# 1-Schematic_Indoor_meteo_sensor.net
KiCad netlist of a schematic drawn in EasyEDA
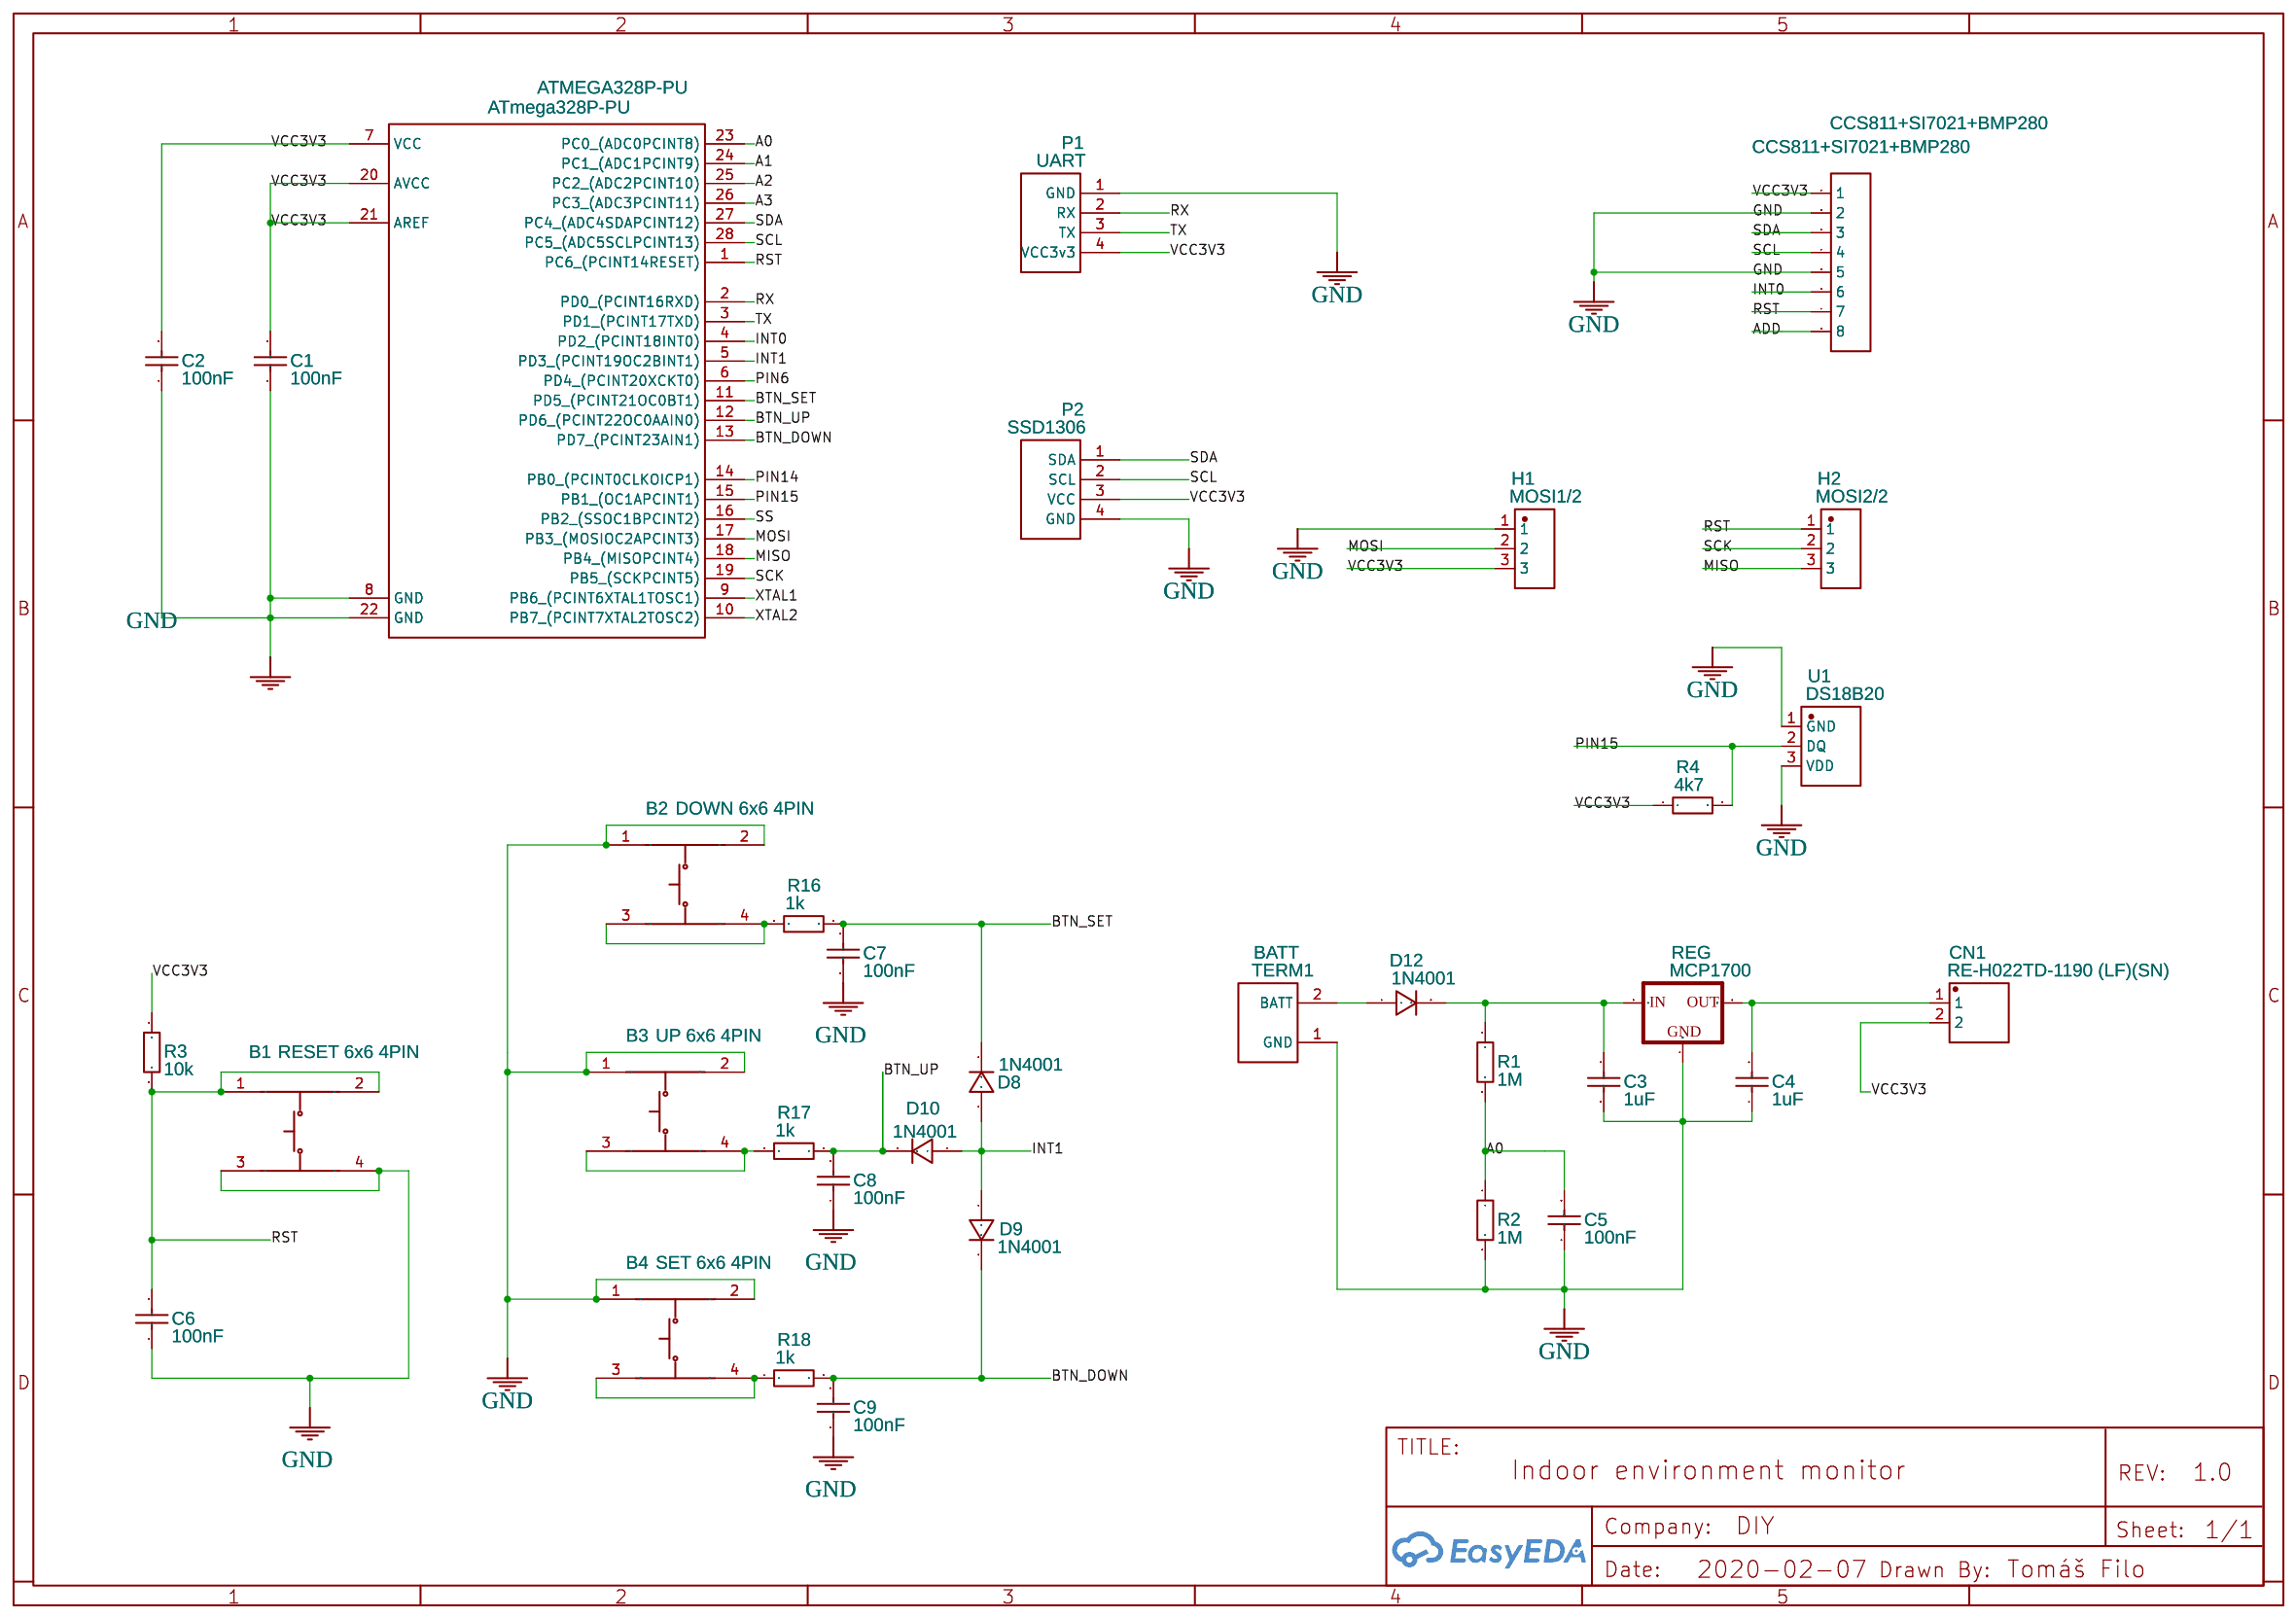
[diagram p0: schematic sheet]

(export (version "E")
  (design (tool "Eeschema 10.0.6"))
  (components
    (comp (ref "ATMEGA328P-PU") (value "ATmega328P-PU") (libsource (lib "") (part "ATmega328P-PU")))
    (comp (ref "B1")
      (value "RESET 6x6 4PIN")
      (fields
        (field (name "BOM_Manufacturer Part") "TC-1102-C-E-B")
        (field (name "BOM_Supplier Part") "C381011")
      )
      (libsource (lib "") (part "Unknown_145_-240"))
    )
    (comp (ref "B2")
      (value "DOWN 6x6 4PIN")
      (fields
        (field (name "BOM_Manufacturer Part") "TC-1102-C-E-B")
        (field (name "BOM_Supplier Part") "C381011")
      )
      (libsource (lib "") (part "Unknown_340_-365"))
    )
    (comp (ref "B3")
      (value "UP 6x6 4PIN")
      (fields
        (field (name "BOM_Manufacturer Part") "TC-1102-C-E-B")
        (field (name "BOM_Supplier Part") "C381011")
      )
      (libsource (lib "") (part "Unknown_330_-250"))
    )
    (comp (ref "B4")
      (value "SET 6x6 4PIN")
      (fields
        (field (name "BOM_Manufacturer Part") "TC-1102-C-E-B")
        (field (name "BOM_Supplier Part") "C381011")
      )
      (libsource (lib "") (part "Unknown_335_-135"))
    )
    (comp (ref "BATT")
      (value "TERM1")
      (fields
        (field (name "BOM_Manufacturer Part") "MKDSN1.5/2-5.08")
        (field (name "BOM_Supplier Part") "C91153")
      )
      (libsource (lib "") (part "Unknown_645_-295"))
    )
    (comp (ref "C1")
      (value "100nF")
      (fields
        (field (name "BOM_Manufacturer Part") "CD1H224KC9BER1E000")
        (field (name "BOM_Supplier Part") "C263191")
      )
      (libsource (lib "") (part "CD1H224KC9BER1E000"))
    )
    (comp (ref "C2")
      (value "100nF")
      (fields
        (field (name "BOM_Manufacturer Part") "CD1H224KC9BER1E000")
        (field (name "BOM_Supplier Part") "C263191")
      )
      (libsource (lib "") (part "CD1H224KC9BER1E000"))
    )
    (comp (ref "C3")
      (value "1uF")
      (fields
        (field (name "BOM_Manufacturer Part") "CD1H224KC9BER1E000")
        (field (name "BOM_Supplier Part") "C263191")
      )
      (libsource (lib "") (part "CD1H224KC9BER1E000"))
    )
    (comp (ref "C4")
      (value "1uF")
      (fields
        (field (name "BOM_Manufacturer Part") "CD1H224KC9BER1E000")
        (field (name "BOM_Supplier Part") "C263191")
      )
      (libsource (lib "") (part "CD1H224KC9BER1E000"))
    )
    (comp (ref "C5")
      (value "100nF")
      (fields
        (field (name "BOM_Manufacturer Part") "CD1H224KC9BER1E000")
        (field (name "BOM_Supplier Part") "C263191")
      )
      (libsource (lib "") (part "CD1H224KC9BER1E000"))
    )
    (comp (ref "C6")
      (value "100nF")
      (fields
        (field (name "BOM_Manufacturer Part") "CD1H224KC9BER1E000")
        (field (name "BOM_Supplier Part") "C263191")
      )
      (libsource (lib "") (part "CD1H224KC9BER1E000"))
    )
    (comp (ref "C7")
      (value "100nF")
      (fields
        (field (name "BOM_Manufacturer Part") "CD1H224KC9BER1E000")
        (field (name "BOM_Supplier Part") "C263191")
      )
      (libsource (lib "") (part "CD1H224KC9BER1E000"))
    )
    (comp (ref "C8")
      (value "100nF")
      (fields
        (field (name "BOM_Manufacturer Part") "CD1H224KC9BER1E000")
        (field (name "BOM_Supplier Part") "C263191")
      )
      (libsource (lib "") (part "CD1H224KC9BER1E000"))
    )
    (comp (ref "C9")
      (value "100nF")
      (fields
        (field (name "BOM_Manufacturer Part") "CD1H224KC9BER1E000")
        (field (name "BOM_Supplier Part") "C263191")
      )
      (libsource (lib "") (part "CD1H224KC9BER1E000"))
    )
    (comp (ref "CCS811+SI7021+BMP280")
      (value "CCS811+SI7021+BMP280")
      (fields
        (field (name "BOM_Manufacturer Part") "Female headerHDR1X8-2.54")
        (field (name "BOM_Supplier Part") "C27438")
      )
      (libsource (lib "") (part "Unknown_925_-680"))
    )
    (comp (ref "CN1")
      (value "RE-H022TD-1190 (LF)(SN)")
      (fields (field (name "BOM_Supplier Part") "C160332"))
      (libsource (lib "") (part "RE-H022TD-1190 (LF)(SN)"))
    )
    (comp (ref "D8")
      (value "1N4001")
      (fields (field (name "BOM_Supplier Part") "C169150"))
      (libsource (lib "") (part "Unknown_490_-265"))
    )
    (comp (ref "D9")
      (value "1N4001")
      (fields (field (name "BOM_Supplier Part") "C169150"))
      (libsource (lib "") (part "Unknown_490_-190"))
    )
    (comp (ref "D10")
      (value "1N4001")
      (fields (field (name "BOM_Supplier Part") "C169150"))
      (libsource (lib "") (part "Unknown_460_-230"))
    )
    (comp (ref "D12")
      (value "1N4001")
      (fields (field (name "BOM_Supplier Part") "C169150"))
      (libsource (lib "") (part "Unknown_705_-305"))
    )
    (comp (ref "H1")
      (value "MOSI1/2")
      (fields
        (field (name "BOM_Manufacturer Part") "22025403P00CKMT")
        (field (name "BOM_Supplier Part") "C146690")
      )
      (libsource (lib "") (part "22025403P00CKMT"))
    )
    (comp (ref "H2")
      (value "MOSI2/2")
      (fields
        (field (name "BOM_Manufacturer Part") "22025403P00CKMT")
        (field (name "BOM_Supplier Part") "C146690")
      )
      (libsource (lib "") (part "22025403P00CKMT"))
    )
    (comp (ref "P1")
      (value "UART")
      (fields
        (field (name "BOM_Manufacturer Part") "220S-1*4P H=8.5MM Ytype Gold-plated")
        (field (name "BOM_Supplier Part") "C124413")
      )
      (libsource (lib "") (part "Unknown_535_-700"))
    )
    (comp (ref "P2")
      (value "SSD1306")
      (fields
        (field (name "BOM_Manufacturer Part") "220S-1*4P H=8.5MM Ytype Gold-plated")
        (field (name "BOM_Supplier Part") "C124413")
      )
      (libsource (lib "") (part "Unknown_535_-565"))
    )
    (comp (ref "R1")
      (value "1M")
      (fields (field (name "BOM_Supplier Part") "C119320"))
      (libsource (lib "") (part "MF1/4W-680Ω±1% T52"))
    )
    (comp (ref "R2")
      (value "1M")
      (fields (field (name "BOM_Supplier Part") "C119320"))
      (libsource (lib "") (part "MF1/4W-680Ω±1% T52"))
    )
    (comp (ref "R3")
      (value "10k")
      (fields (field (name "BOM_Supplier Part") "C119313"))
      (libsource (lib "") (part "MF1/4W-330Ω±1% T52_1"))
    )
    (comp (ref "R4")
      (value "4k7")
      (fields (field (name "BOM_Supplier Part") "C119313"))
      (libsource (lib "") (part "MF1/4W-330Ω±1% T52"))
    )
    (comp (ref "R16")
      (value "1k")
      (fields (field (name "BOM_Supplier Part") "C119313"))
      (libsource (lib "") (part "MF1/4W-330Ω±1% T52"))
    )
    (comp (ref "R17")
      (value "1k")
      (fields (field (name "BOM_Supplier Part") "C119313"))
      (libsource (lib "") (part "MF1/4W-330Ω±1% T52"))
    )
    (comp (ref "R18")
      (value "1k")
      (fields (field (name "BOM_Supplier Part") "C119313"))
      (libsource (lib "") (part "MF1/4W-330Ω±1% T52"))
    )
    (comp (ref "REG") (value "MCP1700") (libsource (lib "") (part "Unknown_845_-295")))
    (comp (ref "U1")
      (value "DS18B20")
      (fields (field (name "BOM_Supplier Part") "C376006"))
      (libsource (lib "") (part "DS18B20"))
    )
  )
  (nets
    (net (code "1") (name "/A0") (class "Default")
      (node (ref "ATMEGA328P-PU") (pin "23") (pinfunction "PC0_(ADC0PCINT8)_23") (pintype "bidirectional"))
      (node (ref "C5") (pin "2") (pinfunction "2_2") (pintype "input"))
      (node (ref "R1") (pin "2") (pinfunction "2_2") (pintype "unspecified"))
      (node (ref "R2") (pin "1") (pinfunction "1_1") (pintype "unspecified"))
    )
    (net (code "2") (name "/A1") (class "Default")
      (node (ref "ATMEGA328P-PU") (pin "24") (pinfunction "PC1_(ADC1PCINT9)_24") (pintype "bidirectional"))
    )
    (net (code "3") (name "/A2") (class "Default")
      (node (ref "ATMEGA328P-PU") (pin "25") (pinfunction "PC2_(ADC2PCINT10)_25") (pintype "bidirectional"))
    )
    (net (code "4") (name "/A3") (class "Default")
      (node (ref "ATMEGA328P-PU") (pin "26") (pinfunction "PC3_(ADC3PCINT11)_26") (pintype "bidirectional"))
    )
    (net (code "5") (name "/ADD") (class "Default")
      (node (ref "CCS811+SI7021+BMP280") (pin "8") (pinfunction "8_8") (pintype "input"))
    )
    (net (code "6") (name "/BTN_DOWN") (class "Default")
      (node (ref "ATMEGA328P-PU") (pin "13") (pinfunction "PD7_(PCINT23AIN1)_13") (pintype "bidirectional"))
      (node (ref "C9") (pin "2") (pinfunction "2_2") (pintype "input"))
      (node (ref "D9") (pin "2") (pinfunction "2_2") (pintype "unspecified"))
      (node (ref "R18") (pin "2") (pinfunction "2_2") (pintype "unspecified"))
    )
    (net (code "7") (name "/BTN_SET") (class "Default")
      (node (ref "ATMEGA328P-PU") (pin "11") (pinfunction "PD5_(PCINT21OC0BT1)_11") (pintype "bidirectional"))
      (node (ref "C7") (pin "2") (pinfunction "2_2") (pintype "input"))
      (node (ref "D8") (pin "2") (pinfunction "2_2") (pintype "unspecified"))
      (node (ref "R16") (pin "2") (pinfunction "2_2") (pintype "unspecified"))
    )
    (net (code "8") (name "/BTN_UP") (class "Default")
      (node (ref "ATMEGA328P-PU") (pin "12") (pinfunction "PD6_(PCINT22OC0AAIN0)_12") (pintype "bidirectional"))
      (node (ref "C8") (pin "2") (pinfunction "2_2") (pintype "input"))
      (node (ref "D10") (pin "2") (pinfunction "2_2") (pintype "unspecified"))
      (node (ref "R17") (pin "2") (pinfunction "2_2") (pintype "unspecified"))
    )
    (net (code "9") (name "/INT0") (class "Default")
      (node (ref "ATMEGA328P-PU") (pin "4") (pinfunction "PD2_(PCINT18INT0)_4") (pintype "bidirectional"))
      (node (ref "CCS811+SI7021+BMP280") (pin "6") (pinfunction "6_6") (pintype "input"))
    )
    (net (code "10") (name "/INT1") (class "Default")
      (node (ref "ATMEGA328P-PU") (pin "5") (pinfunction "PD3_(PCINT19OC2BINT1)_5") (pintype "bidirectional"))
      (node (ref "D10") (pin "1") (pinfunction "1_1") (pintype "unspecified"))
      (node (ref "D8") (pin "1") (pinfunction "1_1") (pintype "unspecified"))
      (node (ref "D9") (pin "1") (pinfunction "1_1") (pintype "unspecified"))
    )
    (net (code "11") (name "/MISO") (class "Default")
      (node (ref "ATMEGA328P-PU") (pin "18") (pinfunction "PB4_(MISOPCINT4)_18") (pintype "bidirectional"))
      (node (ref "H2") (pin "3") (pinfunction "3_3") (pintype "unspecified"))
    )
    (net (code "12") (name "/MOSI") (class "Default")
      (node (ref "ATMEGA328P-PU") (pin "17") (pinfunction "PB3_(MOSIOC2APCINT3)_17") (pintype "bidirectional"))
      (node (ref "H1") (pin "2") (pinfunction "2_2") (pintype "unspecified"))
    )
    (net (code "13") (name "/PIN6") (class "Default")
      (node (ref "ATMEGA328P-PU") (pin "6") (pinfunction "PD4_(PCINT20XCKT0)_6") (pintype "bidirectional"))
    )
    (net (code "14") (name "/PIN14") (class "Default")
      (node (ref "ATMEGA328P-PU") (pin "14") (pinfunction "PB0_(PCINT0CLKOICP1)_14") (pintype "bidirectional"))
    )
    (net (code "15") (name "/PIN15") (class "Default")
      (node (ref "ATMEGA328P-PU") (pin "15") (pinfunction "PB1_(OC1APCINT1)_15") (pintype "bidirectional"))
      (node (ref "R4") (pin "2") (pinfunction "2_2") (pintype "unspecified"))
      (node (ref "U1") (pin "2") (pinfunction "DQ_2") (pintype "unspecified"))
    )
    (net (code "16") (name "/RST") (class "Default")
      (node (ref "ATMEGA328P-PU") (pin "1") (pinfunction "PC6_(PCINT14RESET)_1") (pintype "bidirectional"))
      (node (ref "B1") (pin "1") (pinfunction "1_1") (pintype "unspecified"))
      (node (ref "B1") (pin "2") (pinfunction "2_2") (pintype "unspecified"))
      (node (ref "C6") (pin "2") (pinfunction "2_2") (pintype "input"))
      (node (ref "CCS811+SI7021+BMP280") (pin "7") (pinfunction "7_7") (pintype "input"))
      (node (ref "H2") (pin "1") (pinfunction "1_1") (pintype "unspecified"))
      (node (ref "R3") (pin "2") (pinfunction "2_2") (pintype "unspecified"))
    )
    (net (code "17") (name "/RX") (class "Default")
      (node (ref "ATMEGA328P-PU") (pin "2") (pinfunction "PD0_(PCINT16RXD)_2") (pintype "bidirectional"))
      (node (ref "P1") (pin "2") (pinfunction "RX_2") (pintype "unspecified"))
    )
    (net (code "18") (name "/SCK") (class "Default")
      (node (ref "ATMEGA328P-PU") (pin "19") (pinfunction "PB5_(SCKPCINT5)_19") (pintype "bidirectional"))
      (node (ref "H2") (pin "2") (pinfunction "2_2") (pintype "unspecified"))
    )
    (net (code "19") (name "/SCL") (class "Default")
      (node (ref "ATMEGA328P-PU") (pin "28") (pinfunction "PC5_(ADC5SCLPCINT13)_28") (pintype "bidirectional"))
      (node (ref "CCS811+SI7021+BMP280") (pin "4") (pinfunction "4_4") (pintype "input"))
      (node (ref "P2") (pin "2") (pinfunction "SCL_2") (pintype "unspecified"))
    )
    (net (code "20") (name "/SDA") (class "Default")
      (node (ref "ATMEGA328P-PU") (pin "27") (pinfunction "PC4_(ADC4SDAPCINT12)_27") (pintype "bidirectional"))
      (node (ref "CCS811+SI7021+BMP280") (pin "3") (pinfunction "3_3") (pintype "input"))
      (node (ref "P2") (pin "1") (pinfunction "SDA_1") (pintype "unspecified"))
    )
    (net (code "21") (name "/SS") (class "Default")
      (node (ref "ATMEGA328P-PU") (pin "16") (pinfunction "PB2_(SSOC1BPCINT2)_16") (pintype "bidirectional"))
    )
    (net (code "22") (name "/TX") (class "Default")
      (node (ref "ATMEGA328P-PU") (pin "3") (pinfunction "PD1_(PCINT17TXD)_3") (pintype "bidirectional"))
      (node (ref "P1") (pin "3") (pinfunction "TX_3") (pintype "unspecified"))
    )
    (net (code "23") (name "/VCC3V3") (class "Default")
      (node (ref "ATMEGA328P-PU") (pin "20") (pinfunction "AVCC_20") (pintype "passive"))
      (node (ref "ATMEGA328P-PU") (pin "21") (pinfunction "AREF_21") (pintype "passive"))
      (node (ref "ATMEGA328P-PU") (pin "7") (pinfunction "VCC_7") (pintype "passive"))
      (node (ref "C1") (pin "2") (pinfunction "2_2") (pintype "input"))
      (node (ref "C2") (pin "2") (pinfunction "2_2") (pintype "input"))
      (node (ref "CCS811+SI7021+BMP280") (pin "1") (pinfunction "1_1") (pintype "input"))
      (node (ref "CN1") (pin "2") (pinfunction "2_2") (pintype "unspecified"))
      (node (ref "H1") (pin "3") (pinfunction "3_3") (pintype "unspecified"))
      (node (ref "P1") (pin "4") (pinfunction "VCC3v3_4") (pintype "unspecified"))
      (node (ref "P2") (pin "3") (pinfunction "VCC_3") (pintype "unspecified"))
      (node (ref "R3") (pin "1") (pinfunction "1_1") (pintype "unspecified"))
      (node (ref "R4") (pin "1") (pinfunction "1_1") (pintype "unspecified"))
    )
    (net (code "24") (name "/XTAL1") (class "Default")
      (node (ref "ATMEGA328P-PU") (pin "9") (pinfunction "PB6_(PCINT6XTAL1TOSC1)_9") (pintype "bidirectional"))
    )
    (net (code "25") (name "/XTAL2") (class "Default")
      (node (ref "ATMEGA328P-PU") (pin "10") (pinfunction "PB7_(PCINT7XTAL2TOSC2)_10") (pintype "bidirectional"))
    )
    (net (code "26") (name "GND") (class "Default")
      (node (ref "ATMEGA328P-PU") (pin "22") (pinfunction "GND_22") (pintype "passive"))
      (node (ref "ATMEGA328P-PU") (pin "8") (pinfunction "GND_8") (pintype "passive"))
      (node (ref "B1") (pin "3") (pinfunction "3_3") (pintype "unspecified"))
      (node (ref "B1") (pin "4") (pinfunction "4_4") (pintype "unspecified"))
      (node (ref "B2") (pin "1") (pinfunction "1_1") (pintype "unspecified"))
      (node (ref "B2") (pin "2") (pinfunction "2_2") (pintype "unspecified"))
      (node (ref "B3") (pin "1") (pinfunction "1_1") (pintype "unspecified"))
      (node (ref "B3") (pin "2") (pinfunction "2_2") (pintype "unspecified"))
      (node (ref "B4") (pin "1") (pinfunction "1_1") (pintype "unspecified"))
      (node (ref "B4") (pin "2") (pinfunction "2_2") (pintype "unspecified"))
      (node (ref "BATT") (pin "1") (pinfunction "GND_1") (pintype "unspecified"))
      (node (ref "C1") (pin "1") (pinfunction "1_1") (pintype "input"))
      (node (ref "C2") (pin "1") (pinfunction "1_1") (pintype "input"))
      (node (ref "C3") (pin "1") (pinfunction "1_1") (pintype "input"))
      (node (ref "C4") (pin "1") (pinfunction "1_1") (pintype "input"))
      (node (ref "C5") (pin "1") (pinfunction "1_1") (pintype "input"))
      (node (ref "C6") (pin "1") (pinfunction "1_1") (pintype "input"))
      (node (ref "C7") (pin "1") (pinfunction "1_1") (pintype "input"))
      (node (ref "C8") (pin "1") (pinfunction "1_1") (pintype "input"))
      (node (ref "C9") (pin "1") (pinfunction "1_1") (pintype "input"))
      (node (ref "CCS811+SI7021+BMP280") (pin "2") (pinfunction "2_2") (pintype "input"))
      (node (ref "CCS811+SI7021+BMP280") (pin "5") (pinfunction "5_5") (pintype "input"))
      (node (ref "H1") (pin "1") (pinfunction "1_1") (pintype "unspecified"))
      (node (ref "P1") (pin "1") (pinfunction "GND_1") (pintype "unspecified"))
      (node (ref "P2") (pin "4") (pinfunction "GND_4") (pintype "unspecified"))
      (node (ref "R2") (pin "2") (pinfunction "2_2") (pintype "unspecified"))
      (node (ref "REG") (pin "1") (pinfunction "GND_1") (pintype "input"))
      (node (ref "U1") (pin "1") (pinfunction "GND_1") (pintype "unspecified"))
      (node (ref "U1") (pin "3") (pinfunction "VDD_3") (pintype "unspecified"))
    )
    (net (code "27") (name "Net-(B2-Pad3)") (class "Default")
      (node (ref "B2") (pin "3") (pinfunction "3_3") (pintype "unspecified"))
      (node (ref "B2") (pin "4") (pinfunction "4_4") (pintype "unspecified"))
      (node (ref "R16") (pin "1") (pinfunction "1_1") (pintype "unspecified"))
    )
    (net (code "28") (name "Net-(B3-Pad3)") (class "Default")
      (node (ref "B3") (pin "3") (pinfunction "3_3") (pintype "unspecified"))
      (node (ref "B3") (pin "4") (pinfunction "4_4") (pintype "unspecified"))
      (node (ref "R17") (pin "1") (pinfunction "1_1") (pintype "unspecified"))
    )
    (net (code "29") (name "Net-(B4-Pad3)") (class "Default")
      (node (ref "B4") (pin "3") (pinfunction "3_3") (pintype "unspecified"))
      (node (ref "B4") (pin "4") (pinfunction "4_4") (pintype "unspecified"))
      (node (ref "R18") (pin "1") (pinfunction "1_1") (pintype "unspecified"))
    )
    (net (code "30") (name "Net-(BATT-BATT)") (class "Default")
      (node (ref "BATT") (pin "2") (pinfunction "BATT_2") (pintype "unspecified"))
      (node (ref "D12") (pin "1") (pinfunction "1_1") (pintype "unspecified"))
    )
    (net (code "31") (name "Net-(REG-IN)") (class "Default")
      (node (ref "C3") (pin "2") (pinfunction "2_2") (pintype "input"))
      (node (ref "D12") (pin "2") (pinfunction "2_2") (pintype "unspecified"))
      (node (ref "R1") (pin "1") (pinfunction "1_1") (pintype "unspecified"))
      (node (ref "REG") (pin "2") (pinfunction "IN_2") (pintype "input"))
    )
    (net (code "32") (name "Net-(REG-OUT)") (class "Default")
      (node (ref "C4") (pin "2") (pinfunction "2_2") (pintype "input"))
      (node (ref "CN1") (pin "1") (pinfunction "1_1") (pintype "unspecified"))
      (node (ref "REG") (pin "3") (pinfunction "OUT_3") (pintype "unspecified"))
    )
  )
)
